# mainboard.net
KiCad netlist of a schematic drawn in Altium Designer
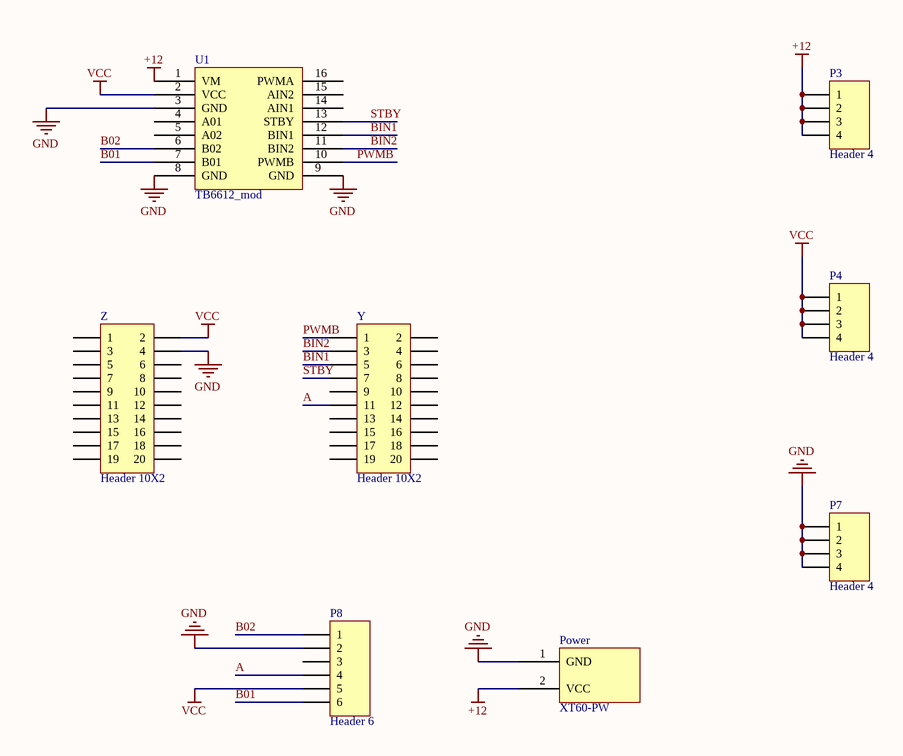
[diagram p0: mainboard.SchDoc]

(export (version "E")
  (design (tool "Eeschema 10.0.6"))
  (components
    (comp (ref "P3")
      (value "Header 4")
      (footprint "HDR1X4")
      (description "Header, 4-Pin")
      (fields (field (name "PUBLISHER") "Altium Limited"))
      (libsource (lib "Miscellaneous Connectors") (part "Header 4"))
    )
    (comp (ref "P4")
      (value "Header 4")
      (footprint "HDR1X4")
      (description "Header, 4-Pin")
      (fields (field (name "PUBLISHER") "Altium Limited"))
      (libsource (lib "Miscellaneous Connectors") (part "Header 4"))
    )
    (comp (ref "P7")
      (value "Header 4")
      (footprint "HDR1X4")
      (description "Header, 4-Pin")
      (fields (field (name "PUBLISHER") "Altium Limited"))
      (libsource (lib "Miscellaneous Connectors") (part "Header 4"))
    )
    (comp (ref "P8")
      (value "Header 6")
      (footprint "HDR1X6")
      (description "Header, 6-Pin")
      (fields (field (name "PUBLISHER") "Altium Limited"))
      (libsource (lib "Miscellaneous Connectors") (part "Header 6"))
    )
    (comp (ref "Power") (value "XT60-PW") (footprint "XT60-PW") (libsource (lib "XT") (part "XT60-PW")))
    (comp (ref "U1") (value "TB6612_mod") (footprint "TB6612_mod") (libsource (lib "XT") (part "TB6612_mod")))
    (comp (ref "Y")
      (value "Header 10X2")
      (footprint "HDR2X10")
      (description "Header, 10-Pin, Dual row")
      (fields (field (name "PUBLISHER") "Altium Limited"))
      (libsource (lib "Miscellaneous Connectors") (part "Header 10X2"))
    )
    (comp (ref "Z")
      (value "Header 10X2")
      (footprint "HDR2X10")
      (description "Header, 10-Pin, Dual row")
      (fields (field (name "PUBLISHER") "Altium Limited"))
      (libsource (lib "Miscellaneous Connectors") (part "Header 10X2"))
    )
  )
  (nets
    (net (code "1") (name "+12") (class "Default")
      (node (ref "P3") (pin "1") (pinfunction "1_1") (pintype "passive"))
      (node (ref "P3") (pin "2") (pinfunction "2_2") (pintype "passive"))
      (node (ref "P3") (pin "3") (pinfunction "3_3") (pintype "passive"))
      (node (ref "P3") (pin "4") (pinfunction "4_4") (pintype "passive"))
      (node (ref "Power") (pin "2") (pinfunction "VCC_2") (pintype "passive"))
      (node (ref "U1") (pin "1") (pinfunction "VM_1") (pintype "passive"))
    )
    (net (code "2") (name "/A") (class "Default")
      (node (ref "P8") (pin "4") (pinfunction "4_4") (pintype "passive"))
      (node (ref "Y") (pin "11") (pinfunction "11_11") (pintype "passive"))
    )
    (net (code "3") (name "/B01") (class "Default")
      (node (ref "P8") (pin "6") (pinfunction "6_6") (pintype "passive"))
      (node (ref "U1") (pin "7") (pinfunction "B01_7") (pintype "passive"))
    )
    (net (code "4") (name "/B02") (class "Default")
      (node (ref "P8") (pin "1") (pinfunction "1_1") (pintype "passive"))
      (node (ref "U1") (pin "6") (pinfunction "B02_6") (pintype "passive"))
    )
    (net (code "5") (name "/BIN1") (class "Default")
      (node (ref "U1") (pin "12") (pinfunction "BIN1_12") (pintype "passive"))
      (node (ref "Y") (pin "5") (pinfunction "5_5") (pintype "passive"))
    )
    (net (code "6") (name "/BIN2") (class "Default")
      (node (ref "U1") (pin "11") (pinfunction "BIN2_11") (pintype "passive"))
      (node (ref "Y") (pin "3") (pinfunction "3_3") (pintype "passive"))
    )
    (net (code "7") (name "/PWMB") (class "Default")
      (node (ref "U1") (pin "10") (pinfunction "PWMB_10") (pintype "passive"))
      (node (ref "Y") (pin "1") (pinfunction "1_1") (pintype "passive"))
    )
    (net (code "8") (name "/STBY") (class "Default")
      (node (ref "U1") (pin "13") (pinfunction "STBY_13") (pintype "passive"))
      (node (ref "Y") (pin "7") (pinfunction "7_7") (pintype "passive"))
    )
    (net (code "9") (name "GND") (class "Default")
      (node (ref "P7") (pin "1") (pinfunction "1_1") (pintype "passive"))
      (node (ref "P7") (pin "2") (pinfunction "2_2") (pintype "passive"))
      (node (ref "P7") (pin "3") (pinfunction "3_3") (pintype "passive"))
      (node (ref "P7") (pin "4") (pinfunction "4_4") (pintype "passive"))
      (node (ref "P8") (pin "2") (pinfunction "2_2") (pintype "passive"))
      (node (ref "Power") (pin "1") (pinfunction "GND_1") (pintype "passive"))
      (node (ref "U1") (pin "3") (pinfunction "GND_3") (pintype "passive"))
      (node (ref "U1") (pin "8") (pinfunction "GND_8") (pintype "passive"))
      (node (ref "U1") (pin "9") (pinfunction "GND_9") (pintype "passive"))
      (node (ref "Z") (pin "4") (pinfunction "4_4") (pintype "passive"))
    )
    (net (code "10") (name "VCC") (class "Default")
      (node (ref "P4") (pin "1") (pinfunction "1_1") (pintype "passive"))
      (node (ref "P4") (pin "2") (pinfunction "2_2") (pintype "passive"))
      (node (ref "P4") (pin "3") (pinfunction "3_3") (pintype "passive"))
      (node (ref "P4") (pin "4") (pinfunction "4_4") (pintype "passive"))
      (node (ref "P8") (pin "5") (pinfunction "5_5") (pintype "passive"))
      (node (ref "U1") (pin "2") (pinfunction "VCC_2") (pintype "passive"))
      (node (ref "Z") (pin "2") (pinfunction "2_2") (pintype "passive"))
    )
    (net (code "11") (name "unconnected-(P8-Pad3)") (class "Default")
      (node (ref "P8") (pin "3") (pinfunction "3_3") (pintype "passive"))
    )
    (net (code "12") (name "unconnected-(U1-A01-Pad4)") (class "Default")
      (node (ref "U1") (pin "4") (pinfunction "A01_4") (pintype "passive"))
    )
    (net (code "13") (name "unconnected-(U1-A02-Pad5)") (class "Default")
      (node (ref "U1") (pin "5") (pinfunction "A02_5") (pintype "passive"))
    )
    (net (code "14") (name "unconnected-(U1-AIN1-Pad14)") (class "Default")
      (node (ref "U1") (pin "14") (pinfunction "AIN1_14") (pintype "passive"))
    )
    (net (code "15") (name "unconnected-(U1-AIN2-Pad15)") (class "Default")
      (node (ref "U1") (pin "15") (pinfunction "AIN2_15") (pintype "passive"))
    )
    (net (code "16") (name "unconnected-(U1-PWMA-Pad16)") (class "Default")
      (node (ref "U1") (pin "16") (pinfunction "PWMA_16") (pintype "passive"))
    )
    (net (code "17") (name "unconnected-(Y-Pad2)") (class "Default")
      (node (ref "Y") (pin "2") (pinfunction "2_2") (pintype "passive"))
    )
    (net (code "18") (name "unconnected-(Y-Pad4)") (class "Default")
      (node (ref "Y") (pin "4") (pinfunction "4_4") (pintype "passive"))
    )
    (net (code "19") (name "unconnected-(Y-Pad6)") (class "Default")
      (node (ref "Y") (pin "6") (pinfunction "6_6") (pintype "passive"))
    )
    (net (code "20") (name "unconnected-(Y-Pad8)") (class "Default")
      (node (ref "Y") (pin "8") (pinfunction "8_8") (pintype "passive"))
    )
    (net (code "21") (name "unconnected-(Y-Pad9)") (class "Default")
      (node (ref "Y") (pin "9") (pinfunction "9_9") (pintype "passive"))
    )
    (net (code "22") (name "unconnected-(Y-Pad10)") (class "Default")
      (node (ref "Y") (pin "10") (pinfunction "10_10") (pintype "passive"))
    )
    (net (code "23") (name "unconnected-(Y-Pad12)") (class "Default")
      (node (ref "Y") (pin "12") (pinfunction "12_12") (pintype "passive"))
    )
    (net (code "24") (name "unconnected-(Y-Pad13)") (class "Default")
      (node (ref "Y") (pin "13") (pinfunction "13_13") (pintype "passive"))
    )
    (net (code "25") (name "unconnected-(Y-Pad14)") (class "Default")
      (node (ref "Y") (pin "14") (pinfunction "14_14") (pintype "passive"))
    )
    (net (code "26") (name "unconnected-(Y-Pad15)") (class "Default")
      (node (ref "Y") (pin "15") (pinfunction "15_15") (pintype "passive"))
    )
    (net (code "27") (name "unconnected-(Y-Pad16)") (class "Default")
      (node (ref "Y") (pin "16") (pinfunction "16_16") (pintype "passive"))
    )
    (net (code "28") (name "unconnected-(Y-Pad17)") (class "Default")
      (node (ref "Y") (pin "17") (pinfunction "17_17") (pintype "passive"))
    )
    (net (code "29") (name "unconnected-(Y-Pad18)") (class "Default")
      (node (ref "Y") (pin "18") (pinfunction "18_18") (pintype "passive"))
    )
    (net (code "30") (name "unconnected-(Y-Pad19)") (class "Default")
      (node (ref "Y") (pin "19") (pinfunction "19_19") (pintype "passive"))
    )
    (net (code "31") (name "unconnected-(Y-Pad20)") (class "Default")
      (node (ref "Y") (pin "20") (pinfunction "20_20") (pintype "passive"))
    )
    (net (code "32") (name "unconnected-(Z-Pad1)") (class "Default")
      (node (ref "Z") (pin "1") (pinfunction "1_1") (pintype "passive"))
    )
    (net (code "33") (name "unconnected-(Z-Pad3)") (class "Default")
      (node (ref "Z") (pin "3") (pinfunction "3_3") (pintype "passive"))
    )
    (net (code "34") (name "unconnected-(Z-Pad5)") (class "Default")
      (node (ref "Z") (pin "5") (pinfunction "5_5") (pintype "passive"))
    )
    (net (code "35") (name "unconnected-(Z-Pad6)") (class "Default")
      (node (ref "Z") (pin "6") (pinfunction "6_6") (pintype "passive"))
    )
    (net (code "36") (name "unconnected-(Z-Pad7)") (class "Default")
      (node (ref "Z") (pin "7") (pinfunction "7_7") (pintype "passive"))
    )
    (net (code "37") (name "unconnected-(Z-Pad8)") (class "Default")
      (node (ref "Z") (pin "8") (pinfunction "8_8") (pintype "passive"))
    )
    (net (code "38") (name "unconnected-(Z-Pad9)") (class "Default")
      (node (ref "Z") (pin "9") (pinfunction "9_9") (pintype "passive"))
    )
    (net (code "39") (name "unconnected-(Z-Pad10)") (class "Default")
      (node (ref "Z") (pin "10") (pinfunction "10_10") (pintype "passive"))
    )
    (net (code "40") (name "unconnected-(Z-Pad11)") (class "Default")
      (node (ref "Z") (pin "11") (pinfunction "11_11") (pintype "passive"))
    )
    (net (code "41") (name "unconnected-(Z-Pad12)") (class "Default")
      (node (ref "Z") (pin "12") (pinfunction "12_12") (pintype "passive"))
    )
    (net (code "42") (name "unconnected-(Z-Pad13)") (class "Default")
      (node (ref "Z") (pin "13") (pinfunction "13_13") (pintype "passive"))
    )
    (net (code "43") (name "unconnected-(Z-Pad14)") (class "Default")
      (node (ref "Z") (pin "14") (pinfunction "14_14") (pintype "passive"))
    )
    (net (code "44") (name "unconnected-(Z-Pad15)") (class "Default")
      (node (ref "Z") (pin "15") (pinfunction "15_15") (pintype "passive"))
    )
    (net (code "45") (name "unconnected-(Z-Pad16)") (class "Default")
      (node (ref "Z") (pin "16") (pinfunction "16_16") (pintype "passive"))
    )
    (net (code "46") (name "unconnected-(Z-Pad17)") (class "Default")
      (node (ref "Z") (pin "17") (pinfunction "17_17") (pintype "passive"))
    )
    (net (code "47") (name "unconnected-(Z-Pad18)") (class "Default")
      (node (ref "Z") (pin "18") (pinfunction "18_18") (pintype "passive"))
    )
    (net (code "48") (name "unconnected-(Z-Pad19)") (class "Default")
      (node (ref "Z") (pin "19") (pinfunction "19_19") (pintype "passive"))
    )
    (net (code "49") (name "unconnected-(Z-Pad20)") (class "Default")
      (node (ref "Z") (pin "20") (pinfunction "20_20") (pintype "passive"))
    )
  )
)
